# USB_Connectors.net
KiCad netlist of a schematic drawn in Altium Designer
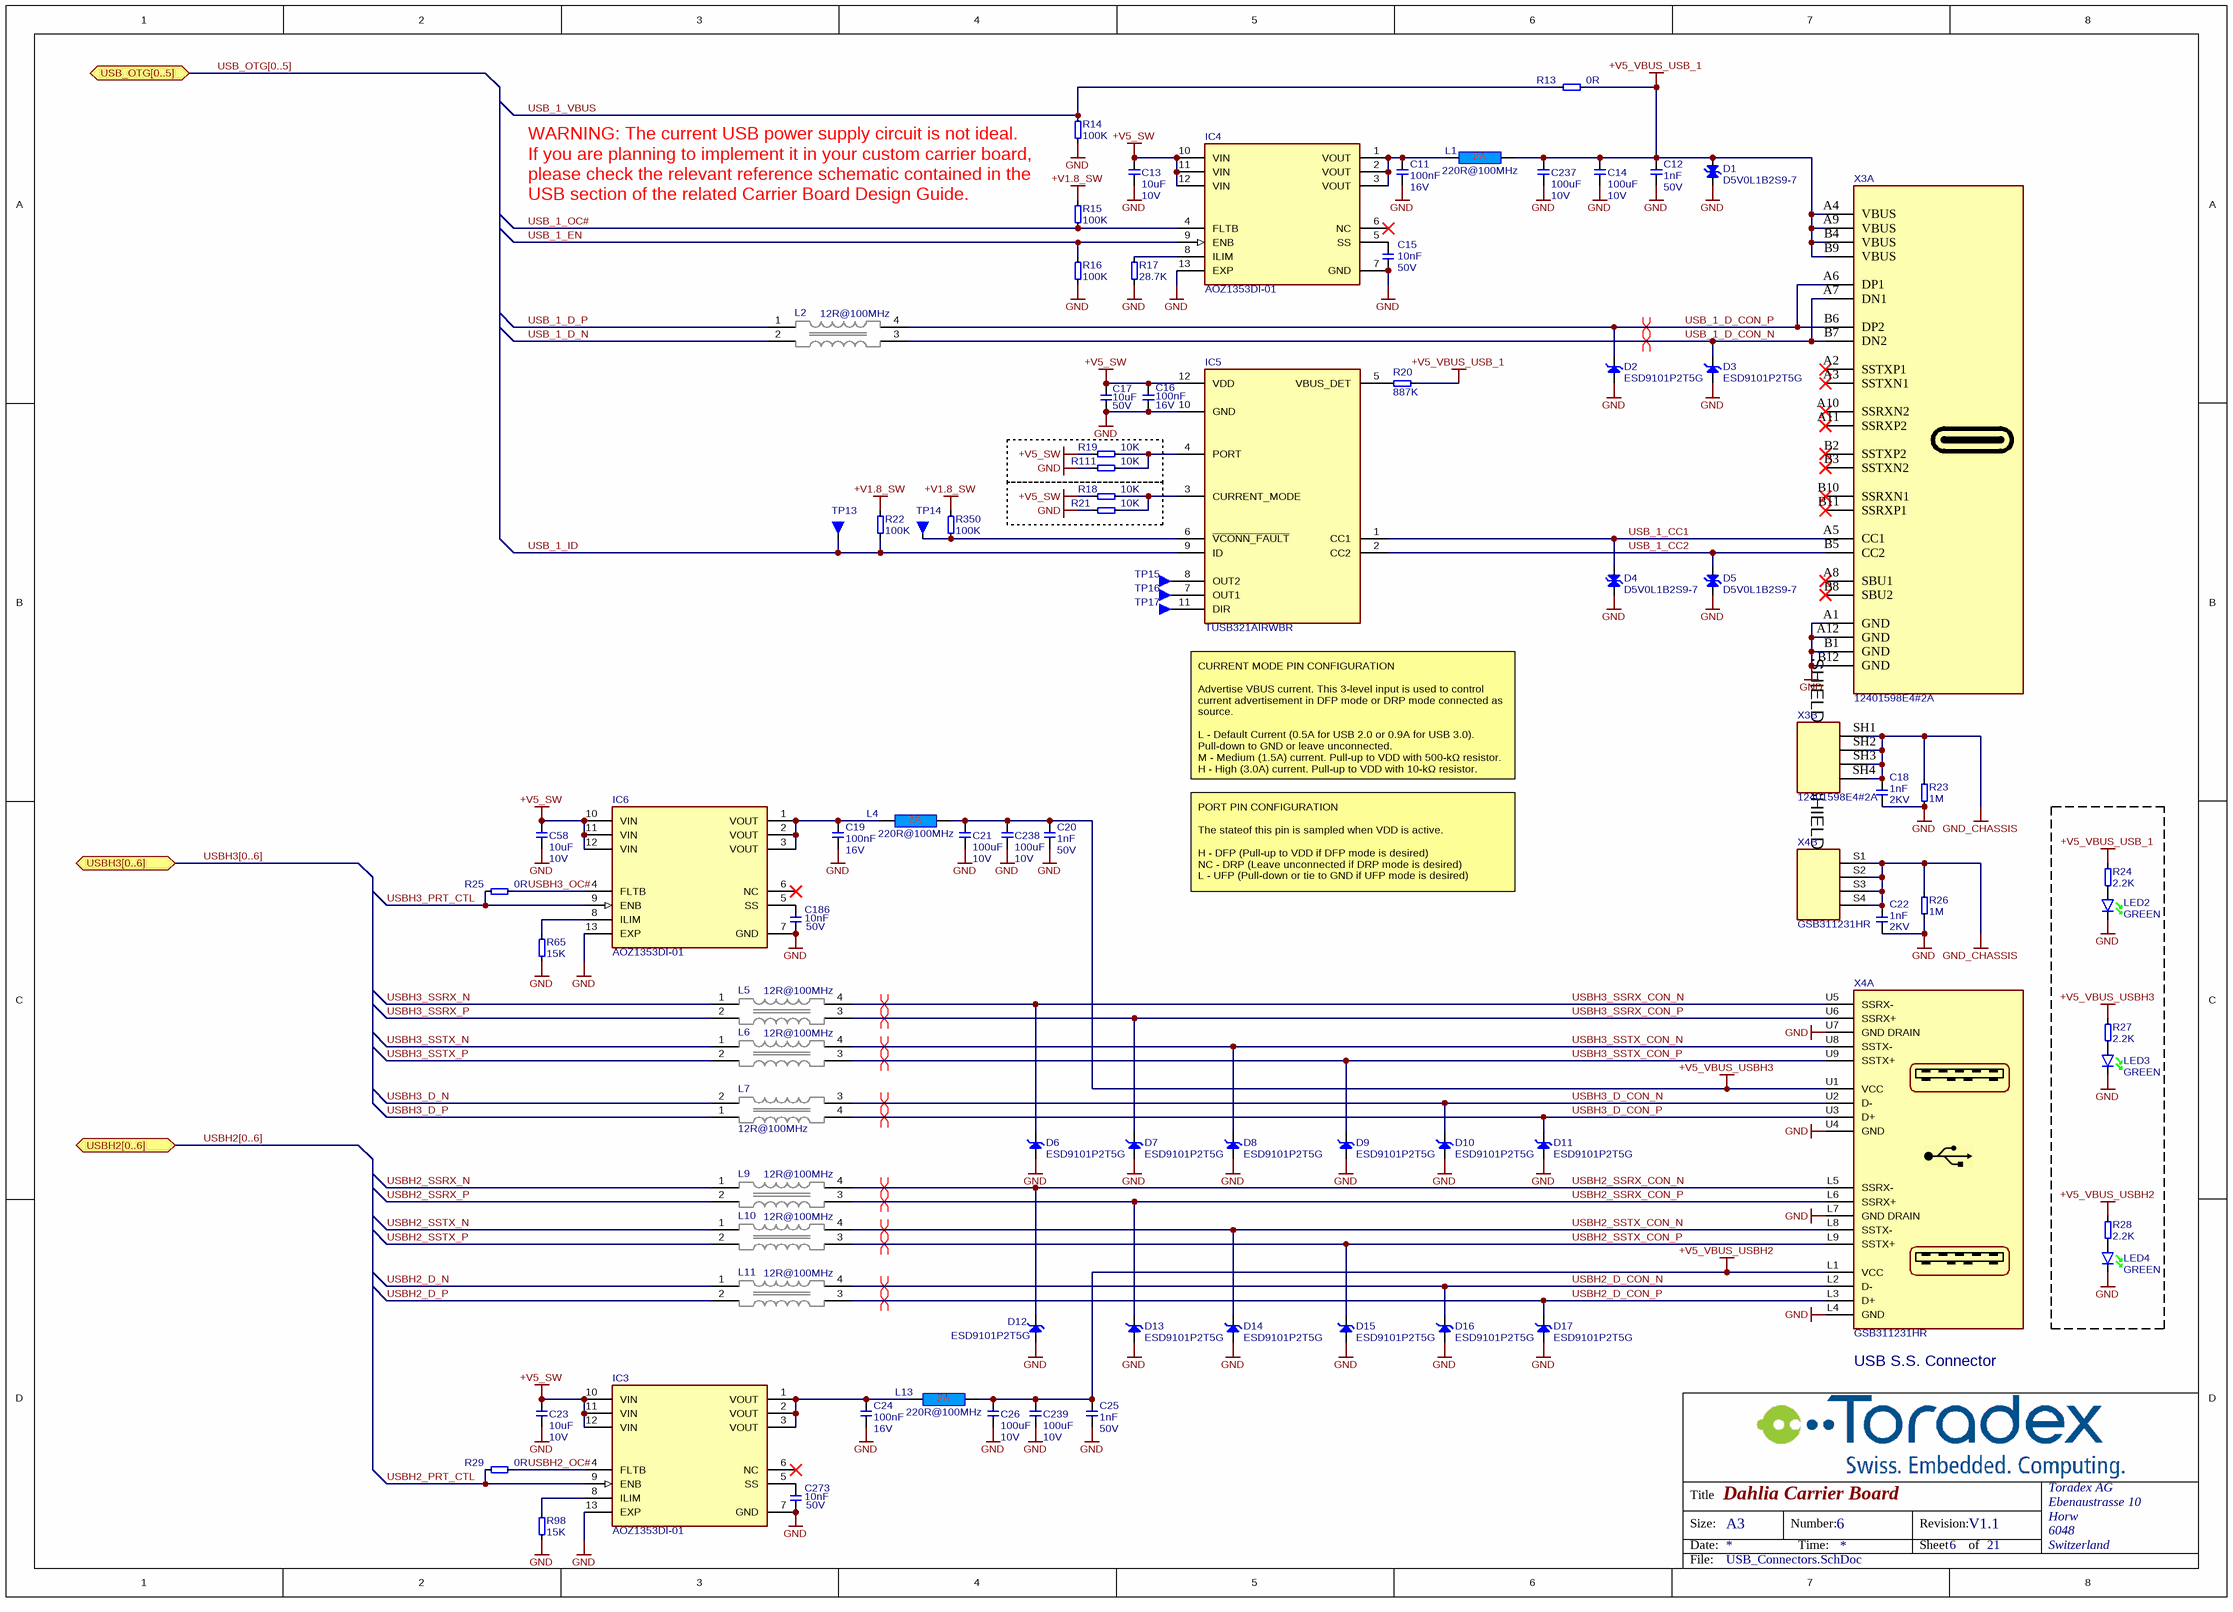
[diagram p0: USB_Connectors.SchDoc]

(export (version "E")
  (design (tool "Eeschema 10.0.6"))
  (components
    (comp (ref "C11")
      (value "100nF")
      (footprint "CAPC1005X60N")
      (description "Capacitor Ceramic X7R 100nF 16V 10% 0402")
      (fields (field (name "TOLERANCE") "10%") (field (name "RATING") "16V"))
      (libsource (lib "Dahlia Carrier Board") (part "C-X7R-100nF-16V-10%-0402"))
    )
    (comp (ref "C12")
      (value "1nF")
      (footprint "CAPC1005X60N")
      (description "Capacitor Ceramic X7R 1nF 50V 10% 0402")
      (fields (field (name "TOLERANCE") "10%") (field (name "RATING") "50V"))
      (libsource (lib "Dahlia Carrier Board") (part "C-X7R-1nF-50V-10%-0402"))
    )
    (comp (ref "C13")
      (value "10uF")
      (footprint "T_CAPC0603X33N")
      (description "Capacitor Ceramic X5R 10uF 10V 20% 0603")
      (fields (field (name "TOLERANCE") "20%") (field (name "RATING") "10V"))
      (libsource (lib "Dahlia Carrier Board") (part "C-X5R-10uF-10V-20%-0603"))
    )
    (comp (ref "C14")
      (value "100uF")
      (footprint "T_CAPC1206X60N")
      (description "Capacitor Ceramic X5R 100uF 10V 20% 1206")
      (fields (field (name "TOLERANCE") "20%") (field (name "RATING") "10V"))
      (libsource (lib "Dahlia Carrier Board") (part "C-X5R-100uF-10V-20%-1206"))
    )
    (comp (ref "C15")
      (value "10nF")
      (footprint "CAPC1005X60N")
      (description "Capacitor Ceramic X7R 10nF 50V 10% 0402")
      (fields (field (name "TOLERANCE") "10%") (field (name "RATING") "50V"))
      (libsource (lib "Dahlia Carrier Board") (part "C-X7R-10nF-50V-10%-0402"))
    )
    (comp (ref "C16")
      (value "100nF")
      (footprint "CAPC1005X60N")
      (description "Capacitor Ceramic X7R 100nF 16V 10% 0402")
      (fields (field (name "TOLERANCE") "10%") (field (name "RATING") "16V"))
      (libsource (lib "Dahlia Carrier Board") (part "C-X7R-100nF-16V-10%-0402"))
    )
    (comp (ref "C17")
      (value "10uF")
      (footprint "T_CAPC1206X60N")
      (description "Capacitor Ceramic X5R 10uF 50V 20% 1206")
      (fields (field (name "TOLERANCE") "20%") (field (name "RATING") "50V"))
      (libsource (lib "Dahlia Carrier Board") (part "C-X5R-10uF-50V-20%-1206"))
    )
    (comp (ref "C18")
      (value "1nF")
      (footprint "T_CAPC1206X180N")
      (description "Capacitor Ceramic X7R 1nF 2KV 10% 1206")
      (fields (field (name "TOLERANCE") "10%") (field (name "RATING") "2KV"))
      (libsource (lib "Dahlia Carrier Board") (part "C-X7R-1nF-2KV-10%-1206"))
    )
    (comp (ref "C19")
      (value "100nF")
      (footprint "CAPC1005X60N")
      (description "Capacitor Ceramic X7R 100nF 16V 10% 0402")
      (fields (field (name "TOLERANCE") "10%") (field (name "RATING") "16V"))
      (libsource (lib "Dahlia Carrier Board") (part "C-X7R-100nF-16V-10%-0402"))
    )
    (comp (ref "C20")
      (value "1nF")
      (footprint "CAPC1005X60N")
      (description "Capacitor Ceramic X7R 1nF 50V 10% 0402")
      (fields (field (name "TOLERANCE") "10%") (field (name "RATING") "50V"))
      (libsource (lib "Dahlia Carrier Board") (part "C-X7R-1nF-50V-10%-0402"))
    )
    (comp (ref "C21")
      (value "100uF")
      (footprint "T_CAPC1206X60N")
      (description "Capacitor Ceramic X5R 100uF 10V 20% 1206")
      (fields (field (name "TOLERANCE") "20%") (field (name "RATING") "10V"))
      (libsource (lib "Dahlia Carrier Board") (part "C-X5R-100uF-10V-20%-1206"))
    )
    (comp (ref "C22")
      (value "1nF")
      (footprint "T_CAPC1206X180N")
      (description "Capacitor Ceramic X7R 1nF 2KV 10% 1206")
      (fields (field (name "TOLERANCE") "10%") (field (name "RATING") "2KV"))
      (libsource (lib "Dahlia Carrier Board") (part "C-X7R-1nF-2KV-10%-1206"))
    )
    (comp (ref "C23")
      (value "10uF")
      (footprint "T_CAPC0603X33N")
      (description "Capacitor Ceramic X5R 10uF 10V 20% 0603")
      (fields (field (name "TOLERANCE") "20%") (field (name "RATING") "10V"))
      (libsource (lib "Dahlia Carrier Board") (part "C-X5R-10uF-10V-20%-0603"))
    )
    (comp (ref "C24")
      (value "100nF")
      (footprint "CAPC1005X60N")
      (description "Capacitor Ceramic X7R 100nF 16V 10% 0402")
      (fields (field (name "TOLERANCE") "10%") (field (name "RATING") "16V"))
      (libsource (lib "Dahlia Carrier Board") (part "C-X7R-100nF-16V-10%-0402"))
    )
    (comp (ref "C25")
      (value "1nF")
      (footprint "CAPC1005X60N")
      (description "Capacitor Ceramic X7R 1nF 50V 10% 0402")
      (fields (field (name "TOLERANCE") "10%") (field (name "RATING") "50V"))
      (libsource (lib "Dahlia Carrier Board") (part "C-X7R-1nF-50V-10%-0402"))
    )
    (comp (ref "C26")
      (value "100uF")
      (footprint "T_CAPC1206X60N")
      (description "Capacitor Ceramic X5R 100uF 10V 20% 1206")
      (fields (field (name "TOLERANCE") "20%") (field (name "RATING") "10V"))
      (libsource (lib "Dahlia Carrier Board") (part "C-X5R-100uF-10V-20%-1206"))
    )
    (comp (ref "C58")
      (value "10uF")
      (footprint "T_CAPC0603X33N")
      (description "Capacitor Ceramic X5R 10uF 10V 20% 0603")
      (fields (field (name "TOLERANCE") "20%") (field (name "RATING") "10V"))
      (libsource (lib "Dahlia Carrier Board") (part "C-X5R-10uF-10V-20%-0603"))
    )
    (comp (ref "C186")
      (value "10nF")
      (footprint "CAPC1005X60N")
      (description "Capacitor Ceramic X7R 10nF 50V 10% 0402")
      (fields (field (name "TOLERANCE") "10%") (field (name "RATING") "50V"))
      (libsource (lib "Dahlia Carrier Board") (part "C-X7R-10nF-50V-10%-0402"))
    )
    (comp (ref "C237")
      (value "100uF")
      (footprint "T_CAPC1206X60N")
      (description "Capacitor Ceramic X5R 100uF 10V 20% 1206")
      (fields (field (name "TOLERANCE") "20%") (field (name "RATING") "10V"))
      (libsource (lib "Dahlia Carrier Board") (part "C-X5R-100uF-10V-20%-1206"))
    )
    (comp (ref "C238")
      (value "100uF")
      (footprint "T_CAPC1206X60N")
      (description "Capacitor Ceramic X5R 100uF 10V 20% 1206")
      (fields (field (name "TOLERANCE") "20%") (field (name "RATING") "10V"))
      (libsource (lib "Dahlia Carrier Board") (part "C-X5R-100uF-10V-20%-1206"))
    )
    (comp (ref "C239")
      (value "100uF")
      (footprint "T_CAPC1206X60N")
      (description "Capacitor Ceramic X5R 100uF 10V 20% 1206")
      (fields (field (name "TOLERANCE") "20%") (field (name "RATING") "10V"))
      (libsource (lib "Dahlia Carrier Board") (part "C-X5R-100uF-10V-20%-1206"))
    )
    (comp (ref "C273")
      (value "10nF")
      (footprint "CAPC1005X60N")
      (description "Capacitor Ceramic X7R 10nF 50V 10% 0402")
      (fields (field (name "TOLERANCE") "10%") (field (name "RATING") "50V"))
      (libsource (lib "Dahlia Carrier Board") (part "C-X7R-10nF-50V-10%-0402"))
    )
    (comp (ref "D1")
      (value "D5V0L1B2S9-7")
      (footprint "D-DIODES-SOD-923")
      (description "BIDIRECTIONAL TVS DIODE 5V  SOD923")
      (fields (field (name "MANUFACTURER PART NO.") "D5V0L1B2S9-7"))
      (libsource (lib "Dahlia Carrier Board") (part "D-Diodes-D5V0L1B2S9-7"))
    )
    (comp (ref "D2")
      (value "ESD9101P2T5G")
      (footprint "SOD-923")
      (description "ESD Protection Diode")
      (fields (field (name "MANUFACTURER PART NO.") "ESD9101P2T5G"))
      (libsource (lib "Dahlia Carrier Board") (part "D-OnSemi-ESD9101P2T5G"))
    )
    (comp (ref "D3")
      (value "ESD9101P2T5G")
      (footprint "SOD-923")
      (description "ESD Protection Diode")
      (fields (field (name "MANUFACTURER PART NO.") "ESD9101P2T5G"))
      (libsource (lib "Dahlia Carrier Board") (part "D-OnSemi-ESD9101P2T5G"))
    )
    (comp (ref "D4")
      (value "D5V0L1B2S9-7")
      (footprint "D-DIODES-SOD-923")
      (description "BIDIRECTIONAL TVS DIODE 5V  SOD923")
      (fields (field (name "MANUFACTURER PART NO.") "D5V0L1B2S9-7"))
      (libsource (lib "Dahlia Carrier Board") (part "D-Diodes-D5V0L1B2S9-7"))
    )
    (comp (ref "D5")
      (value "D5V0L1B2S9-7")
      (footprint "D-DIODES-SOD-923")
      (description "BIDIRECTIONAL TVS DIODE 5V  SOD923")
      (fields (field (name "MANUFACTURER PART NO.") "D5V0L1B2S9-7"))
      (libsource (lib "Dahlia Carrier Board") (part "D-Diodes-D5V0L1B2S9-7"))
    )
    (comp (ref "D6")
      (value "ESD9101P2T5G")
      (footprint "SOD-923")
      (description "ESD Protection Diode")
      (fields (field (name "MANUFACTURER PART NO.") "ESD9101P2T5G"))
      (libsource (lib "Dahlia Carrier Board") (part "D-OnSemi-ESD9101P2T5G"))
    )
    (comp (ref "D7")
      (value "ESD9101P2T5G")
      (footprint "SOD-923")
      (description "ESD Protection Diode")
      (fields (field (name "MANUFACTURER PART NO.") "ESD9101P2T5G"))
      (libsource (lib "Dahlia Carrier Board") (part "D-OnSemi-ESD9101P2T5G"))
    )
    (comp (ref "D8")
      (value "ESD9101P2T5G")
      (footprint "SOD-923")
      (description "ESD Protection Diode")
      (fields (field (name "MANUFACTURER PART NO.") "ESD9101P2T5G"))
      (libsource (lib "Dahlia Carrier Board") (part "D-OnSemi-ESD9101P2T5G"))
    )
    (comp (ref "D9")
      (value "ESD9101P2T5G")
      (footprint "SOD-923")
      (description "ESD Protection Diode")
      (fields (field (name "MANUFACTURER PART NO.") "ESD9101P2T5G"))
      (libsource (lib "Dahlia Carrier Board") (part "D-OnSemi-ESD9101P2T5G"))
    )
    (comp (ref "D10")
      (value "ESD9101P2T5G")
      (footprint "SOD-923")
      (description "ESD Protection Diode")
      (fields (field (name "MANUFACTURER PART NO.") "ESD9101P2T5G"))
      (libsource (lib "Dahlia Carrier Board") (part "D-OnSemi-ESD9101P2T5G"))
    )
    (comp (ref "D11")
      (value "ESD9101P2T5G")
      (footprint "SOD-923")
      (description "ESD Protection Diode")
      (fields (field (name "MANUFACTURER PART NO.") "ESD9101P2T5G"))
      (libsource (lib "Dahlia Carrier Board") (part "D-OnSemi-ESD9101P2T5G"))
    )
    (comp (ref "D12")
      (value "ESD9101P2T5G")
      (footprint "SOD-923")
      (description "ESD Protection Diode")
      (fields (field (name "MANUFACTURER PART NO.") "ESD9101P2T5G"))
      (libsource (lib "Dahlia Carrier Board") (part "D-OnSemi-ESD9101P2T5G"))
    )
    (comp (ref "D13")
      (value "ESD9101P2T5G")
      (footprint "SOD-923")
      (description "ESD Protection Diode")
      (fields (field (name "MANUFACTURER PART NO.") "ESD9101P2T5G"))
      (libsource (lib "Dahlia Carrier Board") (part "D-OnSemi-ESD9101P2T5G"))
    )
    (comp (ref "D14")
      (value "ESD9101P2T5G")
      (footprint "SOD-923")
      (description "ESD Protection Diode")
      (fields (field (name "MANUFACTURER PART NO.") "ESD9101P2T5G"))
      (libsource (lib "Dahlia Carrier Board") (part "D-OnSemi-ESD9101P2T5G"))
    )
    (comp (ref "D15")
      (value "ESD9101P2T5G")
      (footprint "SOD-923")
      (description "ESD Protection Diode")
      (fields (field (name "MANUFACTURER PART NO.") "ESD9101P2T5G"))
      (libsource (lib "Dahlia Carrier Board") (part "D-OnSemi-ESD9101P2T5G"))
    )
    (comp (ref "D16")
      (value "ESD9101P2T5G")
      (footprint "SOD-923")
      (description "ESD Protection Diode")
      (fields (field (name "MANUFACTURER PART NO.") "ESD9101P2T5G"))
      (libsource (lib "Dahlia Carrier Board") (part "D-OnSemi-ESD9101P2T5G"))
    )
    (comp (ref "D17")
      (value "ESD9101P2T5G")
      (footprint "SOD-923")
      (description "ESD Protection Diode")
      (fields (field (name "MANUFACTURER PART NO.") "ESD9101P2T5G"))
      (libsource (lib "Dahlia Carrier Board") (part "D-OnSemi-ESD9101P2T5G"))
    )
    (comp (ref "IC3")
      (value "AOZ1353DI-01")
      (footprint "IC-A&O-AOZ1353DI-01")
      (description "5V/3A  Smart Current Limited Load Switch with True Reverse Current Blocking")
      (fields (field (name "MANUFACTURER PART NO.") "AOZ1353DI-01"))
      (libsource (lib "Dahlia Carrier Board") (part "IC-A&O-AOZ1353DI-01"))
    )
    (comp (ref "IC4")
      (value "AOZ1353DI-01")
      (footprint "IC-A&O-AOZ1353DI-01")
      (description "5V/3A  Smart Current Limited Load Switch with True Reverse Current Blocking")
      (fields (field (name "MANUFACTURER PART NO.") "AOZ1353DI-01"))
      (libsource (lib "Dahlia Carrier Board") (part "IC-A&O-AOZ1353DI-01"))
    )
    (comp (ref "IC5")
      (value "TUSB321AIRWBR")
      (footprint "IC-TI-TUSB321AIRWBR")
      (description "USB Type-C Configuration Channel Logic and Port Control with VCON")
      (fields (field (name "MANUFACTURER PART NO.") "TUSB321AIRWBR"))
      (libsource (lib "Dahlia Carrier Board") (part "IC-TI-TUSB321AIRWBR"))
    )
    (comp (ref "IC6")
      (value "AOZ1353DI-01")
      (footprint "IC-A&O-AOZ1353DI-01")
      (description "5V/3A  Smart Current Limited Load Switch with True Reverse Current Blocking")
      (fields (field (name "MANUFACTURER PART NO.") "AOZ1353DI-01"))
      (libsource (lib "Dahlia Carrier Board") (part "IC-A&O-AOZ1353DI-01"))
    )
    (comp (ref "L1")
      (value "220R@100MHz")
      (footprint "INDC1608X95N")
      (description "220R@100MHz 2A EMI FILTER")
      (fields (field (name "TOLERANCE") "25%"))
      (libsource (lib "Dahlia Carrier Board") (part "L-220R@100MHz-2A-25%-0603"))
    )
    (comp (ref "L2")
      (value "12R@100MHz")
      (footprint "T_Panasonic_EXC14CH120U")
      (description "Common Mode Choke High Speed 12R 100mA")
      (fields (field (name "TOLERANCE") "25%") (field (name "MANUFACTURER PART NO.") "EXC14CH120U"))
      (libsource (lib "") (part "L-Panasonic-EXC14CH120U-12R@100MHz-1000mA-25%_1"))
    )
    (comp (ref "L4")
      (value "220R@100MHz")
      (footprint "INDC1608X95N")
      (description "220R@100MHz 2A EMI FILTER")
      (fields (field (name "TOLERANCE") "25%"))
      (libsource (lib "Dahlia Carrier Board") (part "L-220R@100MHz-2A-25%-0603"))
    )
    (comp (ref "L5")
      (value "12R@100MHz")
      (footprint "T_Panasonic_EXC14CH120U")
      (description "Common Mode Choke High Speed 12R 100mA")
      (fields (field (name "TOLERANCE") "25%") (field (name "MANUFACTURER PART NO.") "EXC14CH120U"))
      (libsource (lib "") (part "L-Panasonic-EXC14CH120U-12R@100MHz-1000mA-25%_1"))
    )
    (comp (ref "L6")
      (value "12R@100MHz")
      (footprint "T_Panasonic_EXC14CH120U")
      (description "Common Mode Choke High Speed 12R 100mA")
      (fields (field (name "TOLERANCE") "25%") (field (name "MANUFACTURER PART NO.") "EXC14CH120U"))
      (libsource (lib "") (part "L-Panasonic-EXC14CH120U-12R@100MHz-1000mA-25%_1"))
    )
    (comp (ref "L7")
      (value "12R@100MHz")
      (footprint "T_Panasonic_EXC14CH120U")
      (description "Common Mode Choke High Speed 12R 100mA")
      (fields (field (name "TOLERANCE") "25%") (field (name "MANUFACTURER PART NO.") "EXC14CH120U"))
      (libsource (lib "Dahlia Carrier Board") (part "L-Panasonic-EXC14CH120U-12R@100MHz-1000mA-25%"))
    )
    (comp (ref "L9")
      (value "12R@100MHz")
      (footprint "T_Panasonic_EXC14CH120U")
      (description "Common Mode Choke High Speed 12R 100mA")
      (fields (field (name "TOLERANCE") "25%") (field (name "MANUFACTURER PART NO.") "EXC14CH120U"))
      (libsource (lib "") (part "L-Panasonic-EXC14CH120U-12R@100MHz-1000mA-25%_1"))
    )
    (comp (ref "L10")
      (value "12R@100MHz")
      (footprint "T_Panasonic_EXC14CH120U")
      (description "Common Mode Choke High Speed 12R 100mA")
      (fields (field (name "TOLERANCE") "25%") (field (name "MANUFACTURER PART NO.") "EXC14CH120U"))
      (libsource (lib "") (part "L-Panasonic-EXC14CH120U-12R@100MHz-1000mA-25%_1"))
    )
    (comp (ref "L11")
      (value "12R@100MHz")
      (footprint "T_Panasonic_EXC14CH120U")
      (description "Common Mode Choke High Speed 12R 100mA")
      (fields (field (name "TOLERANCE") "25%") (field (name "MANUFACTURER PART NO.") "EXC14CH120U"))
      (libsource (lib "") (part "L-Panasonic-EXC14CH120U-12R@100MHz-1000mA-25%_1"))
    )
    (comp (ref "L13")
      (value "220R@100MHz")
      (footprint "INDC1608X95N")
      (description "220R@100MHz 2A EMI FILTER")
      (fields (field (name "TOLERANCE") "25%"))
      (libsource (lib "Dahlia Carrier Board") (part "L-220R@100MHz-2A-25%-0603"))
    )
    (comp (ref "LED2")
      (value "LTST-C190GKT")
      (footprint "T_Liteon_LTST-C190GKT")
      (description "LED green Lite-ON LTST-C190GKT")
      (fields (field (name "COLOR") "GREEN"))
      (libsource (lib "Dahlia Carrier Board") (part "LED-LiteOn-LTST-C190GKT"))
    )
    (comp (ref "LED3")
      (value "LTST-C190GKT")
      (footprint "T_Liteon_LTST-C190GKT")
      (description "LED green Lite-ON LTST-C190GKT")
      (fields (field (name "COLOR") "GREEN"))
      (libsource (lib "Dahlia Carrier Board") (part "LED-LiteOn-LTST-C190GKT"))
    )
    (comp (ref "LED4")
      (value "LTST-C190GKT")
      (footprint "T_Liteon_LTST-C190GKT")
      (description "LED green Lite-ON LTST-C190GKT")
      (fields (field (name "COLOR") "GREEN"))
      (libsource (lib "Dahlia Carrier Board") (part "LED-LiteOn-LTST-C190GKT"))
    )
    (comp (ref "R13")
      (value "0R")
      (footprint "T_RESC0603X30N")
      (description "Resistor 0 ohm 63mW 1% 0603")
      (fields (field (name "TOLERANCE") "1%"))
      (libsource (lib "Dahlia Carrier Board") (part "R-0R-63mW-1%-0603"))
    )
    (comp (ref "R14")
      (value "100K")
      (footprint "RESC1005X40N")
      (description "Resistor 100 Kohm 63mW 5% 0402")
      (fields (field (name "TOLERANCE") "5%"))
      (libsource (lib "Dahlia Carrier Board") (part "R-100K-63mW-5%-0402"))
    )
    (comp (ref "R15")
      (value "100K")
      (footprint "RESC1005X40N")
      (description "Resistor 100 Kohm 63mW 5% 0402")
      (fields (field (name "TOLERANCE") "5%"))
      (libsource (lib "Dahlia Carrier Board") (part "R-100K-63mW-5%-0402"))
    )
    (comp (ref "R16")
      (value "100K")
      (footprint "RESC1005X40N")
      (description "Resistor 100 Kohm 63mW 5% 0402")
      (fields (field (name "TOLERANCE") "5%"))
      (libsource (lib "Dahlia Carrier Board") (part "R-100K-63mW-5%-0402"))
    )
    (comp (ref "R17")
      (value "28.7K")
      (footprint "T_RESC0603X30N")
      (description "Resistor 28.7 Kohm 63mW 1% 0603")
      (fields (field (name "TOLERANCE") "1%"))
      (libsource (lib "Dahlia Carrier Board") (part "R-28.7K-63mW-1%-0603"))
    )
    (comp (ref "R18")
      (value "10K")
      (footprint "T_RESC0603X30N")
      (description "Resistor 10 Kohm 63mW 5% 0603")
      (fields (field (name "TOLERANCE") "5%"))
      (libsource (lib "Dahlia Carrier Board") (part "R-10K-63mW-5%-0603"))
    )
    (comp (ref "R19")
      (value "10K")
      (footprint "T_RESC0603X30N")
      (description "Resistor 10 Kohm 63mW 5% 0603")
      (fields (field (name "TOLERANCE") "5%"))
      (libsource (lib "Dahlia Carrier Board") (part "R-10K-63mW-5%-0603"))
    )
    (comp (ref "R20")
      (value "887K")
      (footprint "RESC1005X40N")
      (description "Resistor 887 Kohm 63mW 1% 0402")
      (fields (field (name "TOLERANCE") "1%"))
      (libsource (lib "Dahlia Carrier Board") (part "R-887K-63mW-1%-0402"))
    )
    (comp (ref "R21")
      (value "10K")
      (footprint "T_RESC0603X30N")
      (description "Resistor 10 Kohm 63mW 5% 0603")
      (fields (field (name "TOLERANCE") "5%"))
      (libsource (lib "Dahlia Carrier Board") (part "R-10K-63mW-5%-0603"))
    )
    (comp (ref "R22")
      (value "100K")
      (footprint "RESC1005X40N")
      (description "Resistor 100 Kohm 63mW 5% 0402")
      (fields (field (name "TOLERANCE") "5%"))
      (libsource (lib "Dahlia Carrier Board") (part "R-100K-63mW-5%-0402"))
    )
    (comp (ref "R23")
      (value "1M")
      (footprint "RESC3216X75N")
      (description "Resistor 1 Mohm 250mW 5% 1206")
      (fields (field (name "TOLERANCE") "5%"))
      (libsource (lib "Dahlia Carrier Board") (part "R-1M-250mW-5%-1206"))
    )
    (comp (ref "R24")
      (value "2.2K")
      (footprint "RESC1005X40N")
      (description "Resistor 2.2 Kohm 63mW 5% 0402")
      (fields (field (name "TOLERANCE") "5%"))
      (libsource (lib "Dahlia Carrier Board") (part "R-2.2K-63mW-5%-0402"))
    )
    (comp (ref "R25")
      (value "0R")
      (footprint "T_RESC0603X30N")
      (description "Resistor 0 ohm 63mW 1% 0603")
      (fields (field (name "TOLERANCE") "1%"))
      (libsource (lib "Dahlia Carrier Board") (part "R-0R-63mW-1%-0603"))
    )
    (comp (ref "R26")
      (value "1M")
      (footprint "RESC3216X75N")
      (description "Resistor 1 Mohm 250mW 5% 1206")
      (fields (field (name "TOLERANCE") "5%"))
      (libsource (lib "Dahlia Carrier Board") (part "R-1M-250mW-5%-1206"))
    )
    (comp (ref "R27")
      (value "2.2K")
      (footprint "RESC1005X40N")
      (description "Resistor 2.2 Kohm 63mW 5% 0402")
      (fields (field (name "TOLERANCE") "5%"))
      (libsource (lib "Dahlia Carrier Board") (part "R-2.2K-63mW-5%-0402"))
    )
    (comp (ref "R28")
      (value "2.2K")
      (footprint "RESC1005X40N")
      (description "Resistor 2.2 Kohm 63mW 5% 0402")
      (fields (field (name "TOLERANCE") "5%"))
      (libsource (lib "Dahlia Carrier Board") (part "R-2.2K-63mW-5%-0402"))
    )
    (comp (ref "R29")
      (value "0R")
      (footprint "T_RESC0603X30N")
      (description "Resistor 0 ohm 63mW 1% 0603")
      (fields (field (name "TOLERANCE") "1%"))
      (libsource (lib "Dahlia Carrier Board") (part "R-0R-63mW-1%-0603"))
    )
    (comp (ref "R65")
      (value "15K")
      (footprint "RESC1005X40N")
      (description "Resistor 15 Kohm 63mW 1% 0402")
      (fields (field (name "TOLERANCE") "1%"))
      (libsource (lib "Dahlia Carrier Board") (part "R-15KR-63mW-1%-0402"))
    )
    (comp (ref "R98")
      (value "15K")
      (footprint "RESC1005X40N")
      (description "Resistor 15 Kohm 63mW 1% 0402")
      (fields (field (name "TOLERANCE") "1%"))
      (libsource (lib "Dahlia Carrier Board") (part "R-15KR-63mW-1%-0402"))
    )
    (comp (ref "R111")
      (value "10K")
      (footprint "T_RESC0603X30N")
      (description "Resistor 10 Kohm 63mW 5% 0603")
      (fields (field (name "TOLERANCE") "5%"))
      (libsource (lib "Dahlia Carrier Board") (part "R-10K-63mW-5%-0603"))
    )
    (comp (ref "R350")
      (value "100K")
      (footprint "RESC1005X40N")
      (description "Resistor 100 Kohm 63mW 5% 0402")
      (fields (field (name "TOLERANCE") "5%"))
      (libsource (lib "Dahlia Carrier Board") (part "R-100K-63mW-5%-0402"))
    )
    (comp (ref "TP13")
      (value "Testpin-SMD")
      (footprint "T_TP-SMD")
      (description "Testpin SMD")
      (libsource (lib "Dahlia Carrier Board") (part "Testpin-SMD"))
    )
    (comp (ref "TP14")
      (value "Testpin-SMD")
      (footprint "T_TP-SMD")
      (description "Testpin SMD")
      (libsource (lib "Dahlia Carrier Board") (part "Testpin-SMD"))
    )
    (comp (ref "TP15")
      (value "Testpin-SMD")
      (footprint "T_TP-SMD")
      (description "Testpin SMD")
      (libsource (lib "Dahlia Carrier Board") (part "Testpin-SMD"))
    )
    (comp (ref "TP16")
      (value "Testpin-SMD")
      (footprint "T_TP-SMD")
      (description "Testpin SMD")
      (libsource (lib "Dahlia Carrier Board") (part "Testpin-SMD"))
    )
    (comp (ref "TP17")
      (value "Testpin-SMD")
      (footprint "T_TP-SMD")
      (description "Testpin SMD")
      (libsource (lib "Dahlia Carrier Board") (part "Testpin-SMD"))
    )
    (comp (ref "X3")
      (value "12401598E4#2A")
      (footprint "CON-AMPHENOL-12401598E4#2A")
      (description "USB 3.1 Gen 2, Input Output Connectors, USB type C, Receptacle, Top mount, dual-row SMT, 1.6mmPCB")
      (fields (field (name "MANUFACTURER PART NO.") "12401598E4#2A"))
      (libsource (lib "Dahlia Carrier Board") (part "CON-Amphenol-12401598E4#2A"))
    )
    (comp (ref "X4")
      (value "GSB311231HR")
      (footprint "T_AMPHENOL_ GSB311231HR")
      (description "USB 3.0 double row, Type A")
      (fields (field (name "MANUFACTURER PART NO.") "GSB311231HR"))
      (libsource (lib "Dahlia Carrier Board") (part "CON-Amphenol-GSB311231HR"))
    )
  )
  (nets
    (net (code "21") (name "+V1.8_SW") (class "Default")
      (node (ref "R15") (pin "2") (pinfunction "2_2") (pintype "passive"))
      (node (ref "R22") (pin "2") (pinfunction "2_2") (pintype "passive"))
      (node (ref "R350") (pin "1") (pinfunction "1_1") (pintype "passive"))
    )
    (net (code "22") (name "+V5_SW") (class "Default")
      (node (ref "C13") (pin "2") (pinfunction "2_2") (pintype "passive"))
      (node (ref "C16") (pin "2") (pinfunction "2_2") (pintype "passive"))
      (node (ref "C17") (pin "2") (pinfunction "2_2") (pintype "passive"))
      (node (ref "C23") (pin "2") (pinfunction "2_2") (pintype "passive"))
      (node (ref "C58") (pin "2") (pinfunction "2_2") (pintype "passive"))
      (node (ref "IC3") (pin "10") (pinfunction "VIN_10") (pintype "power_in"))
      (node (ref "IC3") (pin "11") (pinfunction "VIN_11") (pintype "power_in"))
      (node (ref "IC3") (pin "12") (pinfunction "VIN_12") (pintype "power_in"))
      (node (ref "IC4") (pin "10") (pinfunction "VIN_10") (pintype "power_in"))
      (node (ref "IC4") (pin "11") (pinfunction "VIN_11") (pintype "power_in"))
      (node (ref "IC4") (pin "12") (pinfunction "VIN_12") (pintype "power_in"))
      (node (ref "IC5") (pin "12") (pinfunction "VDD_12") (pintype "power_in"))
      (node (ref "IC6") (pin "10") (pinfunction "VIN_10") (pintype "power_in"))
      (node (ref "IC6") (pin "11") (pinfunction "VIN_11") (pintype "power_in"))
      (node (ref "IC6") (pin "12") (pinfunction "VIN_12") (pintype "power_in"))
      (node (ref "R18") (pin "2") (pinfunction "2_2") (pintype "passive"))
      (node (ref "R19") (pin "2") (pinfunction "2_2") (pintype "passive"))
    )
    (net (code "23") (name "+V5_VBUS_USBH2") (class "Default")
      (node (ref "C239") (pin "2") (pinfunction "2_2") (pintype "passive"))
      (node (ref "C25") (pin "2") (pinfunction "2_2") (pintype "passive"))
      (node (ref "C26") (pin "2") (pinfunction "2_2") (pintype "passive"))
      (node (ref "L13") (pin "2") (pinfunction "2_2") (pintype "passive"))
      (node (ref "R28") (pin "1") (pinfunction "1_1") (pintype "passive"))
      (node (ref "X4") (pin "L1") (pinfunction "VCC_L1") (pintype "power_in"))
    )
    (net (code "24") (name "+V5_VBUS_USBH3") (class "Default")
      (node (ref "C20") (pin "2") (pinfunction "2_2") (pintype "passive"))
      (node (ref "C21") (pin "2") (pinfunction "2_2") (pintype "passive"))
      (node (ref "C238") (pin "2") (pinfunction "2_2") (pintype "passive"))
      (node (ref "L4") (pin "2") (pinfunction "2_2") (pintype "passive"))
      (node (ref "R27") (pin "1") (pinfunction "1_1") (pintype "passive"))
      (node (ref "X4") (pin "U1") (pinfunction "VCC_U1") (pintype "power_in"))
    )
    (net (code "25") (name "+V5_VBUS_USB_1") (class "Default")
      (node (ref "C12") (pin "2") (pinfunction "2_2") (pintype "passive"))
      (node (ref "C14") (pin "2") (pinfunction "2_2") (pintype "passive"))
      (node (ref "C237") (pin "2") (pinfunction "2_2") (pintype "passive"))
      (node (ref "D1") (pin "2") (pinfunction "A_2") (pintype "power_in"))
      (node (ref "L1") (pin "2") (pinfunction "2_2") (pintype "passive"))
      (node (ref "R13") (pin "2") (pinfunction "2_2") (pintype "passive"))
      (node (ref "R20") (pin "2") (pinfunction "2_2") (pintype "passive"))
      (node (ref "R24") (pin "1") (pinfunction "1_1") (pintype "passive"))
      (node (ref "X3") (pin "A4") (pinfunction "VBUS_A4") (pintype "passive"))
      (node (ref "X3") (pin "A9") (pinfunction "VBUS_A9") (pintype "passive"))
      (node (ref "X3") (pin "B4") (pinfunction "VBUS_B4") (pintype "passive"))
      (node (ref "X3") (pin "B9") (pinfunction "VBUS_B9") (pintype "passive"))
    )
    (net (code "27") (name "/USBH2_D_CON_N") (class "Default")
      (node (ref "D16") (pin "1") (pinfunction "C_1") (pintype "power_in"))
      (node (ref "L11") (pin "4") (pinfunction "4_4") (pintype "passive"))
      (node (ref "X4") (pin "L2") (pinfunction "D-_L2") (pintype "passive"))
    )
    (net (code "28") (name "/USBH2_D_CON_P") (class "Default")
      (node (ref "D17") (pin "1") (pinfunction "C_1") (pintype "power_in"))
      (node (ref "L11") (pin "3") (pinfunction "3_3") (pintype "passive"))
      (node (ref "X4") (pin "L3") (pinfunction "D+_L3") (pintype "passive"))
    )
    (net (code "29") (name "/USBH2_D_N") (class "Default")
      (node (ref "L11") (pin "1") (pinfunction "1_1") (pintype "passive"))
    )
    (net (code "30") (name "/USBH2_D_P") (class "Default")
      (node (ref "L11") (pin "2") (pinfunction "2_2") (pintype "passive"))
    )
    (net (code "31") (name "/USBH2_OC#") (class "Default")
      (node (ref "IC3") (pin "4") (pinfunction "FLTB_4") (pintype "passive"))
      (node (ref "R29") (pin "2") (pinfunction "2_2") (pintype "passive"))
    )
    (net (code "32") (name "/USBH2_PRT_CTL") (class "Default")
      (node (ref "IC3") (pin "9") (pinfunction "ENB_9") (pintype "input"))
      (node (ref "R29") (pin "1") (pinfunction "1_1") (pintype "passive"))
    )
    (net (code "33") (name "/USBH2_SSRX_CON_N") (class "Default")
      (node (ref "D12") (pin "1") (pinfunction "C_1") (pintype "power_in"))
      (node (ref "L9") (pin "4") (pinfunction "4_4") (pintype "passive"))
      (node (ref "X4") (pin "L5") (pinfunction "SSRX-_L5") (pintype "power_in"))
    )
    (net (code "34") (name "/USBH2_SSRX_CON_P") (class "Default")
      (node (ref "D13") (pin "1") (pinfunction "C_1") (pintype "power_in"))
      (node (ref "L9") (pin "3") (pinfunction "3_3") (pintype "passive"))
      (node (ref "X4") (pin "L6") (pinfunction "SSRX+_L6") (pintype "power_in"))
    )
    (net (code "35") (name "/USBH2_SSRX_N") (class "Default")
      (node (ref "L9") (pin "1") (pinfunction "1_1") (pintype "passive"))
    )
    (net (code "36") (name "/USBH2_SSRX_P") (class "Default")
      (node (ref "L9") (pin "2") (pinfunction "2_2") (pintype "passive"))
    )
    (net (code "37") (name "/USBH2_SSTX_CON_N") (class "Default")
      (node (ref "D14") (pin "1") (pinfunction "C_1") (pintype "power_in"))
      (node (ref "L10") (pin "4") (pinfunction "4_4") (pintype "passive"))
      (node (ref "X4") (pin "L8") (pinfunction "SSTX-_L8") (pintype "power_in"))
    )
    (net (code "38") (name "/USBH2_SSTX_CON_P") (class "Default")
      (node (ref "D15") (pin "1") (pinfunction "C_1") (pintype "power_in"))
      (node (ref "L10") (pin "3") (pinfunction "3_3") (pintype "passive"))
      (node (ref "X4") (pin "L9") (pinfunction "SSTX+_L9") (pintype "power_in"))
    )
    (net (code "39") (name "/USBH2_SSTX_N") (class "Default")
      (node (ref "L10") (pin "1") (pinfunction "1_1") (pintype "passive"))
    )
    (net (code "40") (name "/USBH2_SSTX_P") (class "Default")
      (node (ref "L10") (pin "2") (pinfunction "2_2") (pintype "passive"))
    )
    (net (code "42") (name "/USBH3_D_CON_N") (class "Default")
      (node (ref "D10") (pin "1") (pinfunction "C_1") (pintype "power_in"))
      (node (ref "L7") (pin "3") (pinfunction "3_3") (pintype "passive"))
      (node (ref "X4") (pin "U2") (pinfunction "D-_U2") (pintype "passive"))
    )
    (net (code "43") (name "/USBH3_D_CON_P") (class "Default")
      (node (ref "D11") (pin "1") (pinfunction "C_1") (pintype "power_in"))
      (node (ref "L7") (pin "4") (pinfunction "4_4") (pintype "passive"))
      (node (ref "X4") (pin "U3") (pinfunction "D+_U3") (pintype "passive"))
    )
    (net (code "44") (name "/USBH3_D_N") (class "Default")
      (node (ref "L7") (pin "2") (pinfunction "2_2") (pintype "passive"))
    )
    (net (code "45") (name "/USBH3_D_P") (class "Default")
      (node (ref "L7") (pin "1") (pinfunction "1_1") (pintype "passive"))
    )
    (net (code "46") (name "/USBH3_OC#") (class "Default")
      (node (ref "IC6") (pin "4") (pinfunction "FLTB_4") (pintype "passive"))
      (node (ref "R25") (pin "2") (pinfunction "2_2") (pintype "passive"))
    )
    (net (code "47") (name "/USBH3_PRT_CTL") (class "Default")
      (node (ref "IC6") (pin "9") (pinfunction "ENB_9") (pintype "input"))
      (node (ref "R25") (pin "1") (pinfunction "1_1") (pintype "passive"))
    )
    (net (code "48") (name "/USBH3_SSRX_CON_N") (class "Default")
      (node (ref "D6") (pin "1") (pinfunction "C_1") (pintype "power_in"))
      (node (ref "L5") (pin "4") (pinfunction "4_4") (pintype "passive"))
      (node (ref "X4") (pin "U5") (pinfunction "SSRX-_U5") (pintype "power_in"))
    )
    (net (code "49") (name "/USBH3_SSRX_CON_P") (class "Default")
      (node (ref "D7") (pin "1") (pinfunction "C_1") (pintype "power_in"))
      (node (ref "L5") (pin "3") (pinfunction "3_3") (pintype "passive"))
      (node (ref "X4") (pin "U6") (pinfunction "SSRX+_U6") (pintype "power_in"))
    )
    (net (code "50") (name "/USBH3_SSRX_N") (class "Default")
      (node (ref "L5") (pin "1") (pinfunction "1_1") (pintype "passive"))
    )
    (net (code "51") (name "/USBH3_SSRX_P") (class "Default")
      (node (ref "L5") (pin "2") (pinfunction "2_2") (pintype "passive"))
    )
    (net (code "52") (name "/USBH3_SSTX_CON_N") (class "Default")
      (node (ref "D8") (pin "1") (pinfunction "C_1") (pintype "power_in"))
      (node (ref "L6") (pin "4") (pinfunction "4_4") (pintype "passive"))
      (node (ref "X4") (pin "U8") (pinfunction "SSTX-_U8") (pintype "power_in"))
    )
    (net (code "53") (name "/USBH3_SSTX_CON_P") (class "Default")
      (node (ref "D9") (pin "1") (pinfunction "C_1") (pintype "power_in"))
      (node (ref "L6") (pin "3") (pinfunction "3_3") (pintype "passive"))
      (node (ref "X4") (pin "U9") (pinfunction "SSTX+_U9") (pintype "power_in"))
    )
    (net (code "54") (name "/USBH3_SSTX_N") (class "Default")
      (node (ref "L6") (pin "1") (pinfunction "1_1") (pintype "passive"))
    )
    (net (code "55") (name "/USBH3_SSTX_P") (class "Default")
      (node (ref "L6") (pin "2") (pinfunction "2_2") (pintype "passive"))
    )
    (net (code "56") (name "/USB_1_CC1") (class "Default")
      (node (ref "D4") (pin "2") (pinfunction "A_2") (pintype "power_in"))
      (node (ref "IC5") (pin "1") (pinfunction "CC1_1") (pintype "power_in"))
      (node (ref "X3") (pin "A5") (pinfunction "CC1_A5") (pintype "passive"))
    )
    (net (code "57") (name "/USB_1_CC2") (class "Default")
      (node (ref "D5") (pin "2") (pinfunction "A_2") (pintype "power_in"))
      (node (ref "IC5") (pin "2") (pinfunction "CC2_2") (pintype "power_in"))
      (node (ref "X3") (pin "B5") (pinfunction "CC2_B5") (pintype "passive"))
    )
    (net (code "58") (name "/USB_1_D_CON_N") (class "Default")
      (node (ref "D3") (pin "1") (pinfunction "C_1") (pintype "power_in"))
      (node (ref "L2") (pin "3") (pinfunction "3_3") (pintype "passive"))
      (node (ref "X3") (pin "A7") (pinfunction "DN1_A7") (pintype "passive"))
      (node (ref "X3") (pin "B7") (pinfunction "DN2_B7") (pintype "passive"))
    )
    (net (code "59") (name "/USB_1_D_CON_P") (class "Default")
      (node (ref "D2") (pin "1") (pinfunction "C_1") (pintype "power_in"))
      (node (ref "L2") (pin "4") (pinfunction "4_4") (pintype "passive"))
      (node (ref "X3") (pin "A6") (pinfunction "DP1_A6") (pintype "passive"))
      (node (ref "X3") (pin "B6") (pinfunction "DP2_B6") (pintype "passive"))
    )
    (net (code "60") (name "/USB_1_D_N") (class "Default")
      (node (ref "L2") (pin "2") (pinfunction "2_2") (pintype "passive"))
    )
    (net (code "61") (name "/USB_1_D_P") (class "Default")
      (node (ref "L2") (pin "1") (pinfunction "1_1") (pintype "passive"))
    )
    (net (code "62") (name "/USB_1_EN") (class "Default")
      (node (ref "IC4") (pin "9") (pinfunction "ENB_9") (pintype "input"))
      (node (ref "R16") (pin "2") (pinfunction "2_2") (pintype "passive"))
    )
    (net (code "63") (name "/USB_1_ID") (class "Default")
      (node (ref "IC5") (pin "9") (pinfunction "ID_9") (pintype "power_in"))
      (node (ref "R22") (pin "1") (pinfunction "1_1") (pintype "passive"))
      (node (ref "TP13") (pin "1") (pinfunction "1_1") (pintype "passive"))
    )
    (net (code "64") (name "/USB_1_OC#") (class "Default")
      (node (ref "IC4") (pin "4") (pinfunction "FLTB_4") (pintype "passive"))
      (node (ref "R15") (pin "1") (pinfunction "1_1") (pintype "passive"))
    )
    (net (code "65") (name "/USB_1_VBUS") (class "Default")
      (node (ref "R13") (pin "1") (pinfunction "1_1") (pintype "passive"))
      (node (ref "R14") (pin "1") (pinfunction "1_1") (pintype "passive"))
    )
    (net (code "67") (name "GND") (class "Default")
      (node (ref "C11") (pin "1") (pinfunction "1_1") (pintype "passive"))
      (node (ref "C12") (pin "1") (pinfunction "1_1") (pintype "passive"))
      (node (ref "C13") (pin "1") (pinfunction "1_1") (pintype "passive"))
      (node (ref "C14") (pin "1") (pinfunction "1_1") (pintype "passive"))
      (node (ref "C15") (pin "1") (pinfunction "1_1") (pintype "passive"))
      (node (ref "C16") (pin "1") (pinfunction "1_1") (pintype "passive"))
      (node (ref "C17") (pin "1") (pinfunction "1_1") (pintype "passive"))
      (node (ref "C18") (pin "1") (pinfunction "1_1") (pintype "passive"))
      (node (ref "C186") (pin "1") (pinfunction "1_1") (pintype "passive"))
      (node (ref "C19") (pin "1") (pinfunction "1_1") (pintype "passive"))
      (node (ref "C20") (pin "1") (pinfunction "1_1") (pintype "passive"))
      (node (ref "C21") (pin "1") (pinfunction "1_1") (pintype "passive"))
      (node (ref "C22") (pin "1") (pinfunction "1_1") (pintype "passive"))
      (node (ref "C23") (pin "1") (pinfunction "1_1") (pintype "passive"))
      (node (ref "C237") (pin "1") (pinfunction "1_1") (pintype "passive"))
      (node (ref "C238") (pin "1") (pinfunction "1_1") (pintype "passive"))
      (node (ref "C239") (pin "1") (pinfunction "1_1") (pintype "passive"))
      (node (ref "C24") (pin "1") (pinfunction "1_1") (pintype "passive"))
      (node (ref "C25") (pin "1") (pinfunction "1_1") (pintype "passive"))
      (node (ref "C26") (pin "1") (pinfunction "1_1") (pintype "passive"))
      (node (ref "C273") (pin "1") (pinfunction "1_1") (pintype "passive"))
      (node (ref "C58") (pin "1") (pinfunction "1_1") (pintype "passive"))
      (node (ref "D1") (pin "1") (pinfunction "C_1") (pintype "power_in"))
      (node (ref "D10") (pin "2") (pinfunction "A_2") (pintype "power_in"))
      (node (ref "D11") (pin "2") (pinfunction "A_2") (pintype "power_in"))
      (node (ref "D12") (pin "2") (pinfunction "A_2") (pintype "power_in"))
      (node (ref "D13") (pin "2") (pinfunction "A_2") (pintype "power_in"))
      (node (ref "D14") (pin "2") (pinfunction "A_2") (pintype "power_in"))
      (node (ref "D15") (pin "2") (pinfunction "A_2") (pintype "power_in"))
      (node (ref "D16") (pin "2") (pinfunction "A_2") (pintype "power_in"))
      (node (ref "D17") (pin "2") (pinfunction "A_2") (pintype "power_in"))
      (node (ref "D2") (pin "2") (pinfunction "A_2") (pintype "power_in"))
      (node (ref "D3") (pin "2") (pinfunction "A_2") (pintype "power_in"))
      (node (ref "D4") (pin "1") (pinfunction "C_1") (pintype "power_in"))
      (node (ref "D5") (pin "1") (pinfunction "C_1") (pintype "power_in"))
      (node (ref "D6") (pin "2") (pinfunction "A_2") (pintype "power_in"))
      (node (ref "D7") (pin "2") (pinfunction "A_2") (pintype "power_in"))
      (node (ref "D8") (pin "2") (pinfunction "A_2") (pintype "power_in"))
      (node (ref "D9") (pin "2") (pinfunction "A_2") (pintype "power_in"))
      (node (ref "IC3") (pin "13") (pinfunction "EXP_13") (pintype "power_in"))
      (node (ref "IC3") (pin "7") (pinfunction "GND_7") (pintype "power_in"))
      (node (ref "IC4") (pin "13") (pinfunction "EXP_13") (pintype "power_in"))
      (node (ref "IC4") (pin "7") (pinfunction "GND_7") (pintype "power_in"))
      (node (ref "IC5") (pin "10") (pinfunction "GND_10") (pintype "power_in"))
      (node (ref "IC6") (pin "13") (pinfunction "EXP_13") (pintype "power_in"))
      (node (ref "IC6") (pin "7") (pinfunction "GND_7") (pintype "power_in"))
      (node (ref "LED2") (pin "K") (pinfunction "K_K") (pintype "passive"))
      (node (ref "LED3") (pin "K") (pinfunction "K_K") (pintype "passive"))
      (node (ref "LED4") (pin "K") (pinfunction "K_K") (pintype "passive"))
      (node (ref "R111") (pin "2") (pinfunction "2_2") (pintype "passive"))
      (node (ref "R14") (pin "2") (pinfunction "2_2") (pintype "passive"))
      (node (ref "R16") (pin "1") (pinfunction "1_1") (pintype "passive"))
      (node (ref "R17") (pin "1") (pinfunction "1_1") (pintype "passive"))
      (node (ref "R21") (pin "2") (pinfunction "2_2") (pintype "passive"))
      (node (ref "R23") (pin "1") (pinfunction "1_1") (pintype "passive"))
      (node (ref "R26") (pin "1") (pinfunction "1_1") (pintype "passive"))
      (node (ref "R65") (pin "1") (pinfunction "1_1") (pintype "passive"))
      (node (ref "R98") (pin "1") (pinfunction "1_1") (pintype "passive"))
      (node (ref "X3") (pin "A1") (pinfunction "GND_A1") (pintype "passive"))
      (node (ref "X3") (pin "A12") (pinfunction "GND_A12") (pintype "passive"))
      (node (ref "X3") (pin "B1") (pinfunction "GND_B1") (pintype "passive"))
      (node (ref "X3") (pin "B12") (pinfunction "GND_B12") (pintype "passive"))
      (node (ref "X4") (pin "L4") (pinfunction "GND_L4") (pintype "power_in"))
      (node (ref "X4") (pin "L7") (pinfunction "GND_DRAIN_L7") (pintype "power_in"))
      (node (ref "X4") (pin "U4") (pinfunction "GND_U4") (pintype "power_in"))
      (node (ref "X4") (pin "U7") (pinfunction "GND_DRAIN_U7") (pintype "power_in"))
    )
    (net (code "68") (name "GND_CHASSIS") (class "Default")
      (node (ref "C18") (pin "2") (pinfunction "2_2") (pintype "passive"))
      (node (ref "C22") (pin "2") (pinfunction "2_2") (pintype "passive"))
      (node (ref "R23") (pin "2") (pinfunction "2_2") (pintype "passive"))
      (node (ref "R26") (pin "2") (pinfunction "2_2") (pintype "passive"))
      (node (ref "X3") (pin "SH1") (pinfunction "SHIELD_SH1") (pintype "passive"))
      (node (ref "X3") (pin "SH2") (pinfunction "SHIELD_SH2") (pintype "passive"))
      (node (ref "X3") (pin "SH3") (pinfunction "SHIELD_SH3") (pintype "passive"))
      (node (ref "X3") (pin "SH4") (pinfunction "SHIELD_SH4") (pintype "passive"))
      (node (ref "X4") (pin "S1") (pinfunction "SHIELD_S1") (pintype "passive"))
      (node (ref "X4") (pin "S2") (pinfunction "SHIELD_S2") (pintype "passive"))
      (node (ref "X4") (pin "S3") (pinfunction "SHIELD_S3") (pintype "passive"))
      (node (ref "X4") (pin "S4") (pinfunction "SHIELD_S4") (pintype "passive"))
    )
    (net (code "69") (name "Net-(C11-Pad2)") (class "Default")
      (node (ref "C11") (pin "2") (pinfunction "2_2") (pintype "passive"))
      (node (ref "IC4") (pin "1") (pinfunction "VOUT_1") (pintype "power_in"))
      (node (ref "IC4") (pin "2") (pinfunction "VOUT_2") (pintype "power_in"))
      (node (ref "IC4") (pin "3") (pinfunction "VOUT_3") (pintype "power_in"))
      (node (ref "L1") (pin "1") (pinfunction "1_1") (pintype "passive"))
    )
    (net (code "70") (name "Net-(C19-Pad2)") (class "Default")
      (node (ref "C19") (pin "2") (pinfunction "2_2") (pintype "passive"))
      (node (ref "IC6") (pin "1") (pinfunction "VOUT_1") (pintype "power_in"))
      (node (ref "IC6") (pin "2") (pinfunction "VOUT_2") (pintype "power_in"))
      (node (ref "IC6") (pin "3") (pinfunction "VOUT_3") (pintype "power_in"))
      (node (ref "L4") (pin "1") (pinfunction "1_1") (pintype "passive"))
    )
    (net (code "71") (name "Net-(C24-Pad2)") (class "Default")
      (node (ref "C24") (pin "2") (pinfunction "2_2") (pintype "passive"))
      (node (ref "IC3") (pin "1") (pinfunction "VOUT_1") (pintype "power_in"))
      (node (ref "IC3") (pin "2") (pinfunction "VOUT_2") (pintype "power_in"))
      (node (ref "IC3") (pin "3") (pinfunction "VOUT_3") (pintype "power_in"))
      (node (ref "L13") (pin "1") (pinfunction "1_1") (pintype "passive"))
    )
    (net (code "72") (name "Net-(IC3-ILIM)") (class "Default")
      (node (ref "IC3") (pin "8") (pinfunction "ILIM_8") (pintype "passive"))
      (node (ref "R98") (pin "2") (pinfunction "2_2") (pintype "passive"))
    )
    (net (code "73") (name "Net-(IC3-SS)") (class "Default")
      (node (ref "C273") (pin "2") (pinfunction "2_2") (pintype "passive"))
      (node (ref "IC3") (pin "5") (pinfunction "SS_5") (pintype "passive"))
    )
    (net (code "74") (name "Net-(IC4-ILIM)") (class "Default")
      (node (ref "IC4") (pin "8") (pinfunction "ILIM_8") (pintype "passive"))
      (node (ref "R17") (pin "2") (pinfunction "2_2") (pintype "passive"))
    )
    (net (code "75") (name "Net-(IC4-SS)") (class "Default")
      (node (ref "C15") (pin "2") (pinfunction "2_2") (pintype "passive"))
      (node (ref "IC4") (pin "5") (pinfunction "SS_5") (pintype "passive"))
    )
    (net (code "76") (name "Net-(IC5-CURRENT_MODE)") (class "Default")
      (node (ref "IC5") (pin "3") (pinfunction "CURRENT_MODE_3") (pintype "power_in"))
      (node (ref "R18") (pin "1") (pinfunction "1_1") (pintype "passive"))
      (node (ref "R21") (pin "1") (pinfunction "1_1") (pintype "passive"))
    )
    (net (code "77") (name "Net-(IC5-DIR)") (class "Default")
      (node (ref "IC5") (pin "11") (pinfunction "DIR_11") (pintype "power_in"))
      (node (ref "TP17") (pin "1") (pinfunction "1_1") (pintype "passive"))
    )
    (net (code "78") (name "Net-(IC5-OUT1)") (class "Default")
      (node (ref "IC5") (pin "7") (pinfunction "OUT1_7") (pintype "power_in"))
      (node (ref "TP16") (pin "1") (pinfunction "1_1") (pintype "passive"))
    )
    (net (code "79") (name "Net-(IC5-OUT2)") (class "Default")
      (node (ref "IC5") (pin "8") (pinfunction "OUT2_8") (pintype "power_in"))
      (node (ref "TP15") (pin "1") (pinfunction "1_1") (pintype "passive"))
    )
    (net (code "80") (name "Net-(IC5-PORT)") (class "Default")
      (node (ref "IC5") (pin "4") (pinfunction "PORT_4") (pintype "power_in"))
      (node (ref "R111") (pin "1") (pinfunction "1_1") (pintype "passive"))
      (node (ref "R19") (pin "1") (pinfunction "1_1") (pintype "passive"))
    )
    (net (code "81") (name "Net-(IC5-VBUS_DET)") (class "Default")
      (node (ref "IC5") (pin "5") (pinfunction "VBUS_DET_5") (pintype "power_in"))
      (node (ref "R20") (pin "1") (pinfunction "1_1") (pintype "passive"))
    )
    (net (code "82") (name "Net-(IC5-~{VCONN_FAULT})") (class "Default")
      (node (ref "IC5") (pin "6") (pinfunction "~{VCONN_FAULT}_6") (pintype "power_in"))
      (node (ref "R350") (pin "2") (pinfunction "2_2") (pintype "passive"))
      (node (ref "TP14") (pin "1") (pinfunction "1_1") (pintype "passive"))
    )
    (net (code "83") (name "Net-(IC6-ILIM)") (class "Default")
      (node (ref "IC6") (pin "8") (pinfunction "ILIM_8") (pintype "passive"))
      (node (ref "R65") (pin "2") (pinfunction "2_2") (pintype "passive"))
    )
    (net (code "84") (name "Net-(IC6-SS)") (class "Default")
      (node (ref "C186") (pin "2") (pinfunction "2_2") (pintype "passive"))
      (node (ref "IC6") (pin "5") (pinfunction "SS_5") (pintype "passive"))
    )
    (net (code "85") (name "Net-(LED2-PadA)") (class "Default")
      (node (ref "LED2") (pin "A") (pinfunction "A_A") (pintype "passive"))
      (node (ref "R24") (pin "2") (pinfunction "2_2") (pintype "passive"))
    )
    (net (code "86") (name "Net-(LED3-PadA)") (class "Default")
      (node (ref "LED3") (pin "A") (pinfunction "A_A") (pintype "passive"))
      (node (ref "R27") (pin "2") (pinfunction "2_2") (pintype "passive"))
    )
    (net (code "87") (name "Net-(LED4-PadA)") (class "Default")
      (node (ref "LED4") (pin "A") (pinfunction "A_A") (pintype "passive"))
      (node (ref "R28") (pin "2") (pinfunction "2_2") (pintype "passive"))
    )
    (net (code "88") (name "unconnected-(IC3-NC-Pad6)") (class "Default")
      (node (ref "IC3") (pin "6") (pinfunction "NC_6") (pintype "passive+no_connect"))
    )
    (net (code "89") (name "unconnected-(IC4-NC-Pad6)") (class "Default")
      (node (ref "IC4") (pin "6") (pinfunction "NC_6") (pintype "passive+no_connect"))
    )
    (net (code "90") (name "unconnected-(IC6-NC-Pad6)") (class "Default")
      (node (ref "IC6") (pin "6") (pinfunction "NC_6") (pintype "passive+no_connect"))
    )
    (net (code "91") (name "unconnected-(X3A-SBU1-PadA8)") (class "Default")
      (node (ref "X3") (pin "A8") (pinfunction "SBU1_A8") (pintype "passive+no_connect"))
    )
    (net (code "92") (name "unconnected-(X3A-SBU2-PadB8)") (class "Default")
      (node (ref "X3") (pin "B8") (pinfunction "SBU2_B8") (pintype "passive+no_connect"))
    )
    (net (code "93") (name "unconnected-(X3A-SSRXN1-PadB10)") (class "Default")
      (node (ref "X3") (pin "B10") (pinfunction "SSRXN1_B10") (pintype "passive+no_connect"))
    )
    (net (code "94") (name "unconnected-(X3A-SSRXN2-PadA10)") (class "Default")
      (node (ref "X3") (pin "A10") (pinfunction "SSRXN2_A10") (pintype "passive+no_connect"))
    )
    (net (code "95") (name "unconnected-(X3A-SSRXP1-PadB11)") (class "Default")
      (node (ref "X3") (pin "B11") (pinfunction "SSRXP1_B11") (pintype "passive+no_connect"))
    )
    (net (code "96") (name "unconnected-(X3A-SSRXP2-PadA11)") (class "Default")
      (node (ref "X3") (pin "A11") (pinfunction "SSRXP2_A11") (pintype "passive+no_connect"))
    )
    (net (code "97") (name "unconnected-(X3A-SSTXN1-PadA3)") (class "Default")
      (node (ref "X3") (pin "A3") (pinfunction "SSTXN1_A3") (pintype "passive+no_connect"))
    )
    (net (code "98") (name "unconnected-(X3A-SSTXN2-PadB3)") (class "Default")
      (node (ref "X3") (pin "B3") (pinfunction "SSTXN2_B3") (pintype "passive+no_connect"))
    )
    (net (code "99") (name "unconnected-(X3A-SSTXP1-PadA2)") (class "Default")
      (node (ref "X3") (pin "A2") (pinfunction "SSTXP1_A2") (pintype "passive+no_connect"))
    )
    (net (code "100") (name "unconnected-(X3A-SSTXP2-PadB2)") (class "Default")
      (node (ref "X3") (pin "B2") (pinfunction "SSTXP2_B2") (pintype "passive+no_connect"))
    )
  )
)
